# Secure_ESP8266.net
KiCad netlist of a schematic drawn in EAGLE
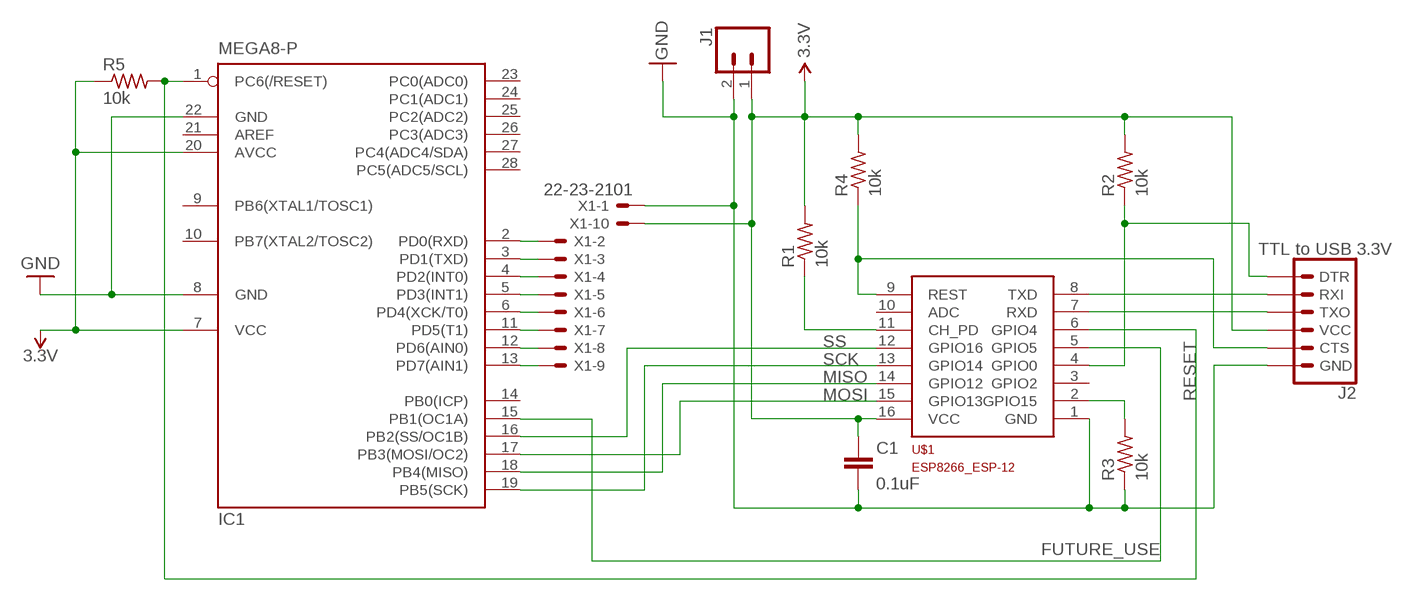
[diagram p0: schematic, sheet 1]

(export (version "E")
  (design (tool "Eeschema 10.0.6"))
  (components
    (comp (ref "C1")
      (value "0.1uF")
      (footprint "eagle-import:CAP-PTH-SMALL-KIT")
      (libsource (lib "eagle-import") (part "0.1UF-KIT-EZ-50V-20%"))
    )
    (comp (ref "IC1")
      (value "MEGA8-P")
      (footprint "eagle-import:DIL28-3")
      (libsource (lib "eagle-import") (part "MEGA8-P"))
    )
    (comp (ref "J1")
      (value "CONN_02PTH3")
      (footprint "eagle-import:1X02_LONGPADS")
      (libsource (lib "eagle-import") (part "CONN_02PTH3"))
    )
    (comp (ref "J2")
      (value "TTL to USB 3.3V")
      (footprint "eagle-import:1X06_LONGPADS")
      (libsource (lib "eagle-import") (part "6_PIN_SERIAL_TARGETLONGPADS"))
    )
    (comp (ref "R1")
      (value "10k")
      (footprint "eagle-import:0204_7")
      (libsource (lib "eagle-import") (part "R-US_0204/7"))
    )
    (comp (ref "R2")
      (value "10k")
      (footprint "eagle-import:0204_7")
      (libsource (lib "eagle-import") (part "R-US_0204/7"))
    )
    (comp (ref "R3")
      (value "10k")
      (footprint "eagle-import:0204_7")
      (libsource (lib "eagle-import") (part "R-US_0204/7"))
    )
    (comp (ref "R4")
      (value "10k")
      (footprint "eagle-import:0204_7")
      (libsource (lib "eagle-import") (part "R-US_0204/7"))
    )
    (comp (ref "R5")
      (value "10k")
      (footprint "eagle-import:0204_7")
      (libsource (lib "eagle-import") (part "R-US_0204/7"))
    )
    (comp (ref "U$1")
      (value "ESP8266_ESP-12")
      (footprint "eagle-import:ESP8266-ESP12")
      (libsource (lib "eagle-import") (part "ESP8266_ESP-12"))
    )
    (comp (ref "X1")
      (value "22-23-2101")
      (footprint "eagle-import:22-23-2101")
      (fields (field (name "MF") "MOLEX"))
      (libsource (lib "eagle-import") (part "22-23-2101"))
    )
  )
  (nets
    (net (code "1") (name "/FUTURE_USE") (class "Default")
      (node (ref "IC1") (pin "15") (pinfunction "PB1(OC1A)_15") (pintype "bidirectional"))
      (node (ref "U$1") (pin "5") (pinfunction "GPIO5_5") (pintype "bidirectional"))
    )
    (net (code "2") (name "/MISO") (class "Default")
      (node (ref "IC1") (pin "18") (pinfunction "PB4(MISO)_18") (pintype "bidirectional"))
      (node (ref "U$1") (pin "14") (pinfunction "GPIO12_14") (pintype "bidirectional"))
    )
    (net (code "3") (name "/MOSI") (class "Default")
      (node (ref "IC1") (pin "17") (pinfunction "PB3(MOSI/OC2)_17") (pintype "bidirectional"))
      (node (ref "U$1") (pin "15") (pinfunction "GPIO13_15") (pintype "bidirectional"))
    )
    (net (code "4") (name "/RESET") (class "Default")
      (node (ref "IC1") (pin "1") (pinfunction "PC6(/RESET)_1") (pintype "bidirectional"))
      (node (ref "R5") (pin "2") (pinfunction "2_2") (pintype "passive"))
      (node (ref "U$1") (pin "6") (pinfunction "GPIO4_6") (pintype "bidirectional"))
    )
    (net (code "5") (name "/SCK") (class "Default")
      (node (ref "IC1") (pin "19") (pinfunction "PB5(SCK)_19") (pintype "bidirectional"))
      (node (ref "U$1") (pin "13") (pinfunction "GPIO14_13") (pintype "bidirectional"))
    )
    (net (code "6") (name "/SS") (class "Default")
      (node (ref "IC1") (pin "16") (pinfunction "PB2(SS/OC1B)_16") (pintype "bidirectional"))
      (node (ref "U$1") (pin "12") (pinfunction "GPIO16_12") (pintype "bidirectional"))
    )
    (net (code "7") (name "3.3V") (class "Default")
      (node (ref "C1") (pin "2") (pinfunction "2_2") (pintype "passive"))
      (node (ref "IC1") (pin "20") (pinfunction "AVCC_20") (pintype "power_in"))
      (node (ref "IC1") (pin "7") (pinfunction "VCC_7") (pintype "power_in"))
      (node (ref "J1") (pin "1") (pinfunction "1_1") (pintype "passive"))
      (node (ref "J2") (pin "4") (pinfunction "VCC_4") (pintype "passive"))
      (node (ref "R1") (pin "2") (pinfunction "2_2") (pintype "passive"))
      (node (ref "R2") (pin "2") (pinfunction "2_2") (pintype "passive"))
      (node (ref "R4") (pin "2") (pinfunction "2_2") (pintype "passive"))
      (node (ref "R5") (pin "1") (pinfunction "1_1") (pintype "passive"))
      (node (ref "U$1") (pin "16") (pinfunction "VCC_16") (pintype "bidirectional"))
      (node (ref "X1") (pin "10") (pinfunction "S_10") (pintype "passive"))
    )
    (net (code "8") (name "GND") (class "Default")
      (node (ref "C1") (pin "1") (pinfunction "1_1") (pintype "passive"))
      (node (ref "IC1") (pin "22") (pinfunction "GND_22") (pintype "power_in"))
      (node (ref "IC1") (pin "8") (pinfunction "GND_8") (pintype "power_in"))
      (node (ref "J1") (pin "2") (pinfunction "2_2") (pintype "passive"))
      (node (ref "J2") (pin "6") (pinfunction "GND_6") (pintype "passive"))
      (node (ref "R3") (pin "1") (pinfunction "1_1") (pintype "passive"))
      (node (ref "U$1") (pin "1") (pinfunction "GND_1") (pintype "bidirectional"))
      (node (ref "X1") (pin "1") (pinfunction "S_1") (pintype "passive"))
    )
    (net (code "9") (name "Net-(IC1-PD0(RXD))") (class "Default")
      (node (ref "IC1") (pin "2") (pinfunction "PD0(RXD)_2") (pintype "bidirectional"))
      (node (ref "X1") (pin "2") (pinfunction "S_2") (pintype "passive"))
    )
    (net (code "10") (name "Net-(IC1-PD1(TXD))") (class "Default")
      (node (ref "IC1") (pin "3") (pinfunction "PD1(TXD)_3") (pintype "bidirectional"))
      (node (ref "X1") (pin "3") (pinfunction "S_3") (pintype "passive"))
    )
    (net (code "11") (name "Net-(IC1-PD2(INT0))") (class "Default")
      (node (ref "IC1") (pin "4") (pinfunction "PD2(INT0)_4") (pintype "bidirectional"))
      (node (ref "X1") (pin "4") (pinfunction "S_4") (pintype "passive"))
    )
    (net (code "12") (name "Net-(IC1-PD3(INT1))") (class "Default")
      (node (ref "IC1") (pin "5") (pinfunction "PD3(INT1)_5") (pintype "bidirectional"))
      (node (ref "X1") (pin "5") (pinfunction "S_5") (pintype "passive"))
    )
    (net (code "13") (name "Net-(IC1-PD4(XCK{slash}T0))") (class "Default")
      (node (ref "IC1") (pin "6") (pinfunction "PD4(XCK/T0)_6") (pintype "bidirectional"))
      (node (ref "X1") (pin "6") (pinfunction "S_6") (pintype "passive"))
    )
    (net (code "14") (name "Net-(IC1-PD5(T1))") (class "Default")
      (node (ref "IC1") (pin "11") (pinfunction "PD5(T1)_11") (pintype "bidirectional"))
      (node (ref "X1") (pin "7") (pinfunction "S_7") (pintype "passive"))
    )
    (net (code "15") (name "Net-(IC1-PD6(AIN0))") (class "Default")
      (node (ref "IC1") (pin "12") (pinfunction "PD6(AIN0)_12") (pintype "bidirectional"))
      (node (ref "X1") (pin "8") (pinfunction "S_8") (pintype "passive"))
    )
    (net (code "16") (name "Net-(IC1-PD7(AIN1))") (class "Default")
      (node (ref "IC1") (pin "13") (pinfunction "PD7(AIN1)_13") (pintype "bidirectional"))
      (node (ref "X1") (pin "9") (pinfunction "S_9") (pintype "passive"))
    )
    (net (code "17") (name "Net-(J2-CTS)") (class "Default")
      (node (ref "J2") (pin "5") (pinfunction "CTS_5") (pintype "passive"))
      (node (ref "R4") (pin "1") (pinfunction "1_1") (pintype "passive"))
      (node (ref "U$1") (pin "9") (pinfunction "REST_9") (pintype "bidirectional"))
    )
    (net (code "18") (name "Net-(J2-DTR)") (class "Default")
      (node (ref "J2") (pin "1") (pinfunction "DTR_1") (pintype "passive"))
      (node (ref "R2") (pin "1") (pinfunction "1_1") (pintype "passive"))
      (node (ref "U$1") (pin "4") (pinfunction "GPIO0_4") (pintype "bidirectional"))
    )
    (net (code "19") (name "Net-(J2-RXI)") (class "Default")
      (node (ref "J2") (pin "2") (pinfunction "RXI_2") (pintype "passive"))
      (node (ref "U$1") (pin "8") (pinfunction "TXD_8") (pintype "bidirectional"))
    )
    (net (code "20") (name "Net-(J2-TXO)") (class "Default")
      (node (ref "J2") (pin "3") (pinfunction "TXO_3") (pintype "passive"))
      (node (ref "U$1") (pin "7") (pinfunction "RXD_7") (pintype "bidirectional"))
    )
    (net (code "21") (name "Net-(U$1-CH_PD)") (class "Default")
      (node (ref "R1") (pin "1") (pinfunction "1_1") (pintype "passive"))
      (node (ref "U$1") (pin "11") (pinfunction "CH_PD_11") (pintype "bidirectional"))
    )
    (net (code "22") (name "Net-(U$1-GPIO15)") (class "Default")
      (node (ref "R3") (pin "2") (pinfunction "2_2") (pintype "passive"))
      (node (ref "U$1") (pin "2") (pinfunction "GPIO15_2") (pintype "bidirectional"))
    )
    (net (code "23") (name "unconnected-(IC1-AREF-Pad21)") (class "Default")
      (node (ref "IC1") (pin "21") (pinfunction "AREF_21") (pintype "passive"))
    )
    (net (code "24") (name "unconnected-(IC1-PB0(ICP)-Pad14)") (class "Default")
      (node (ref "IC1") (pin "14") (pinfunction "PB0(ICP)_14") (pintype "bidirectional"))
    )
    (net (code "25") (name "unconnected-(IC1-PB6(XTAL1{slash}TOSC1)-Pad9)") (class "Default")
      (node (ref "IC1") (pin "9") (pinfunction "PB6(XTAL1/TOSC1)_9") (pintype "bidirectional"))
    )
    (net (code "26") (name "unconnected-(IC1-PB7(XTAL2{slash}TOSC2)-Pad10)") (class "Default")
      (node (ref "IC1") (pin "10") (pinfunction "PB7(XTAL2/TOSC2)_10") (pintype "bidirectional"))
    )
    (net (code "27") (name "unconnected-(IC1-PC0(ADC0)-Pad23)") (class "Default")
      (node (ref "IC1") (pin "23") (pinfunction "PC0(ADC0)_23") (pintype "bidirectional"))
    )
    (net (code "28") (name "unconnected-(IC1-PC1(ADC1)-Pad24)") (class "Default")
      (node (ref "IC1") (pin "24") (pinfunction "PC1(ADC1)_24") (pintype "bidirectional"))
    )
    (net (code "29") (name "unconnected-(IC1-PC2(ADC2)-Pad25)") (class "Default")
      (node (ref "IC1") (pin "25") (pinfunction "PC2(ADC2)_25") (pintype "bidirectional"))
    )
    (net (code "30") (name "unconnected-(IC1-PC3(ADC3)-Pad26)") (class "Default")
      (node (ref "IC1") (pin "26") (pinfunction "PC3(ADC3)_26") (pintype "bidirectional"))
    )
    (net (code "31") (name "unconnected-(IC1-PC4(ADC4{slash}SDA)-Pad27)") (class "Default")
      (node (ref "IC1") (pin "27") (pinfunction "PC4(ADC4/SDA)_27") (pintype "bidirectional"))
    )
    (net (code "32") (name "unconnected-(IC1-PC5(ADC5{slash}SCL)-Pad28)") (class "Default")
      (node (ref "IC1") (pin "28") (pinfunction "PC5(ADC5/SCL)_28") (pintype "bidirectional"))
    )
    (net (code "33") (name "unconnected-(U$1-ADC-Pad10)") (class "Default")
      (node (ref "U$1") (pin "10") (pinfunction "ADC_10") (pintype "bidirectional"))
    )
    (net (code "34") (name "unconnected-(U$1-GPIO2-Pad3)") (class "Default")
      (node (ref "U$1") (pin "3") (pinfunction "GPIO2_3") (pintype "bidirectional"))
    )
  )
)
